# Adafruit_SharpMemoryDisplay.net
KiCad netlist of a schematic drawn in EAGLE
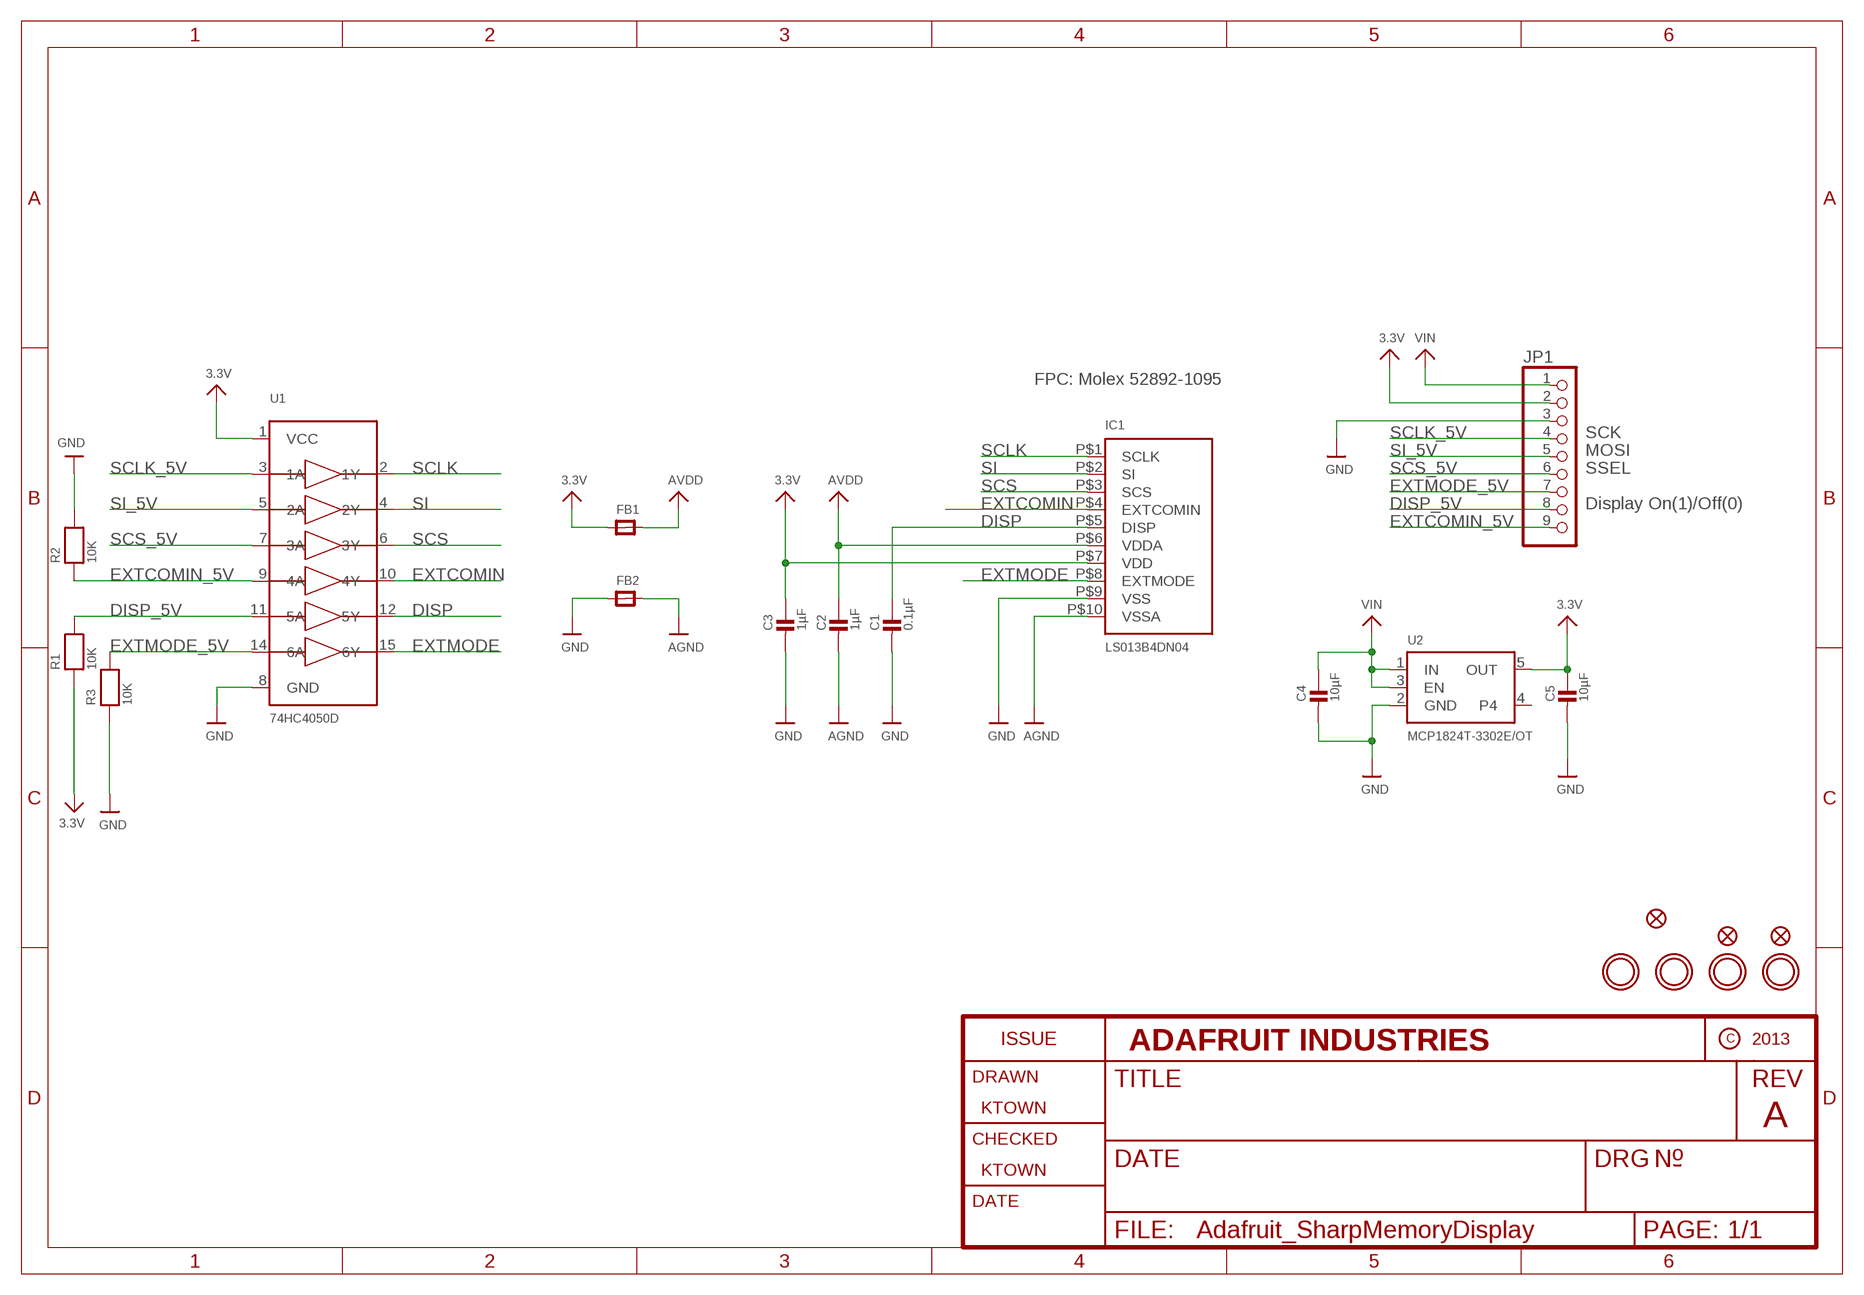
[diagram p0: schematic, sheet 1]

(export (version "E")
  (design (tool "Eeschema 10.0.6"))
  (components
    (comp (ref "C1")
      (value "0.1µF")
      (footprint "eagle-import:_0805")
      (libsource (lib "eagle-import") (part "CAP_CERAMIC_0805"))
    )
    (comp (ref "C2")
      (value "1µF")
      (footprint "eagle-import:_0805")
      (libsource (lib "eagle-import") (part "CAP_CERAMIC_0805"))
    )
    (comp (ref "C3")
      (value "1µF")
      (footprint "eagle-import:_0805")
      (libsource (lib "eagle-import") (part "CAP_CERAMIC_0805"))
    )
    (comp (ref "C4")
      (value "10µF")
      (footprint "eagle-import:_0805")
      (libsource (lib "eagle-import") (part "CAP_CERAMIC_0805"))
    )
    (comp (ref "C5")
      (value "10µF")
      (footprint "eagle-import:_0805")
      (libsource (lib "eagle-import") (part "CAP_CERAMIC_0805"))
    )
    (comp (ref "FB1")
      (value "FERRITE_0805")
      (footprint "eagle-import:_0805")
      (libsource (lib "eagle-import") (part "FERRITE_0805"))
    )
    (comp (ref "FB2")
      (value "FERRITE_0805")
      (footprint "eagle-import:_0805")
      (libsource (lib "eagle-import") (part "FERRITE_0805"))
    )
    (comp (ref "FID1")
      (value "FIDUCIAL\"\"")
      (footprint "eagle-import:FIDUCIAL_1MM")
      (libsource (lib "eagle-import") (part "FIDUCIAL{dblquote}{dblquote}"))
    )
    (comp (ref "FID2")
      (value "FIDUCIAL\"\"")
      (footprint "eagle-import:FIDUCIAL_1MM")
      (libsource (lib "eagle-import") (part "FIDUCIAL{dblquote}{dblquote}"))
    )
    (comp (ref "FID3")
      (value "FIDUCIAL\"\"")
      (footprint "eagle-import:FIDUCIAL_1MM")
      (libsource (lib "eagle-import") (part "FIDUCIAL{dblquote}{dblquote}"))
    )
    (comp (ref "IC1")
      (value "LS013B4DN04")
      (footprint "eagle-import:FPC_10PIN_52892-1095")
      (libsource (lib "eagle-import") (part "SHARP_MEMORYLCD_10PIN"))
    )
    (comp (ref "JP1")
      (value "HEADER-1X970MIL")
      (footprint "eagle-import:1X09_ROUND_70")
      (libsource (lib "eagle-import") (part "HEADER-1X970MIL"))
    )
    (comp (ref "R1")
      (value "10K")
      (footprint "eagle-import:_0805")
      (libsource (lib "eagle-import") (part "RESISTOR_0805"))
    )
    (comp (ref "R2")
      (value "10K")
      (footprint "eagle-import:_0805")
      (libsource (lib "eagle-import") (part "RESISTOR_0805"))
    )
    (comp (ref "R3")
      (value "10K")
      (footprint "eagle-import:_0805")
      (libsource (lib "eagle-import") (part "RESISTOR_0805"))
    )
    (comp (ref "U$21")
      (value "MOUNTINGHOLE3.0THIN")
      (footprint "eagle-import:MOUNTINGHOLE_3.0_PLATEDTHIN")
      (libsource (lib "eagle-import") (part "MOUNTINGHOLE3.0THIN"))
    )
    (comp (ref "U$22")
      (value "MOUNTINGHOLE3.0THIN")
      (footprint "eagle-import:MOUNTINGHOLE_3.0_PLATEDTHIN")
      (libsource (lib "eagle-import") (part "MOUNTINGHOLE3.0THIN"))
    )
    (comp (ref "U$27")
      (value "MOUNTINGHOLE3.0THIN")
      (footprint "eagle-import:MOUNTINGHOLE_3.0_PLATEDTHIN")
      (libsource (lib "eagle-import") (part "MOUNTINGHOLE3.0THIN"))
    )
    (comp (ref "U$28")
      (value "MOUNTINGHOLE3.0THIN")
      (footprint "eagle-import:MOUNTINGHOLE_3.0_PLATEDTHIN")
      (libsource (lib "eagle-import") (part "MOUNTINGHOLE3.0THIN"))
    )
    (comp (ref "U1")
      (value "74HC4050D")
      (footprint "eagle-import:SOIC16")
      (libsource (lib "eagle-import") (part "74HC4050D"))
    )
    (comp (ref "U2")
      (value "MCP1824T-3302E/OT")
      (footprint "eagle-import:SOT23-5")
      (libsource (lib "eagle-import") (part "VREG_SOT23-5"))
    )
  )
  (nets
    (net (code "1") (name "/DISP") (class "Default")
      (node (ref "C1") (pin "1") (pinfunction "P$1_1") (pintype "passive"))
      (node (ref "IC1") (pin "P$5") (pinfunction "DISP_P$5") (pintype "input"))
      (node (ref "U1") (pin "12") (pinfunction "5Y_12") (pintype "bidirectional"))
    )
    (net (code "2") (name "/DISP_5V") (class "Default")
      (node (ref "JP1") (pin "8") (pinfunction "8_8") (pintype "passive"))
      (node (ref "R1") (pin "2") (pinfunction "2_2") (pintype "passive"))
      (node (ref "U1") (pin "11") (pinfunction "5A_11") (pintype "bidirectional"))
    )
    (net (code "3") (name "/EXTCOMIN") (class "Default")
      (node (ref "IC1") (pin "P$4") (pinfunction "EXTCOMIN_P$4") (pintype "input"))
      (node (ref "U1") (pin "10") (pinfunction "4Y_10") (pintype "bidirectional"))
    )
    (net (code "4") (name "/EXTCOMIN_5V") (class "Default")
      (node (ref "JP1") (pin "9") (pinfunction "9_9") (pintype "passive"))
      (node (ref "R2") (pin "1") (pinfunction "1_1") (pintype "passive"))
      (node (ref "U1") (pin "9") (pinfunction "4A_9") (pintype "bidirectional"))
    )
    (net (code "5") (name "/EXTMODE") (class "Default")
      (node (ref "IC1") (pin "P$8") (pinfunction "EXTMODE_P$8") (pintype "input"))
      (node (ref "U1") (pin "15") (pinfunction "6Y_15") (pintype "bidirectional"))
    )
    (net (code "6") (name "/EXTMODE_5V") (class "Default")
      (node (ref "JP1") (pin "7") (pinfunction "7_7") (pintype "passive"))
      (node (ref "R3") (pin "2") (pinfunction "2_2") (pintype "passive"))
      (node (ref "U1") (pin "14") (pinfunction "6A_14") (pintype "bidirectional"))
    )
    (net (code "7") (name "/SCLK") (class "Default")
      (node (ref "IC1") (pin "P$1") (pinfunction "SCLK_P$1") (pintype "input"))
      (node (ref "U1") (pin "2") (pinfunction "1Y_2") (pintype "bidirectional"))
    )
    (net (code "8") (name "/SCLK_5V") (class "Default")
      (node (ref "JP1") (pin "4") (pinfunction "4_4") (pintype "passive"))
      (node (ref "U1") (pin "3") (pinfunction "1A_3") (pintype "bidirectional"))
    )
    (net (code "9") (name "/SCS") (class "Default")
      (node (ref "IC1") (pin "P$3") (pinfunction "SCS_P$3") (pintype "input"))
      (node (ref "U1") (pin "6") (pinfunction "3Y_6") (pintype "bidirectional"))
    )
    (net (code "10") (name "/SCS_5V") (class "Default")
      (node (ref "JP1") (pin "6") (pinfunction "6_6") (pintype "passive"))
      (node (ref "U1") (pin "7") (pinfunction "3A_7") (pintype "bidirectional"))
    )
    (net (code "11") (name "/SI") (class "Default")
      (node (ref "IC1") (pin "P$2") (pinfunction "SI_P$2") (pintype "input"))
      (node (ref "U1") (pin "4") (pinfunction "2Y_4") (pintype "bidirectional"))
    )
    (net (code "12") (name "/SI_5V") (class "Default")
      (node (ref "JP1") (pin "5") (pinfunction "5_5") (pintype "passive"))
      (node (ref "U1") (pin "5") (pinfunction "2A_5") (pintype "bidirectional"))
    )
    (net (code "13") (name "3.3V") (class "Default")
      (node (ref "C3") (pin "1") (pinfunction "P$1_1") (pintype "passive"))
      (node (ref "C5") (pin "1") (pinfunction "P$1_1") (pintype "passive"))
      (node (ref "FB1") (pin "1") (pinfunction "P$1_1") (pintype "passive"))
      (node (ref "IC1") (pin "P$7") (pinfunction "VDD_P$7") (pintype "power_in"))
      (node (ref "JP1") (pin "2") (pinfunction "2_2") (pintype "passive"))
      (node (ref "R1") (pin "1") (pinfunction "1_1") (pintype "passive"))
      (node (ref "U1") (pin "1") (pinfunction "VCC_1") (pintype "bidirectional"))
      (node (ref "U2") (pin "5") (pinfunction "OUT_5") (pintype "power_in"))
    )
    (net (code "14") (name "AGND") (class "Default")
      (node (ref "C2") (pin "2") (pinfunction "P$2_2") (pintype "passive"))
      (node (ref "FB2") (pin "2") (pinfunction "P$2_2") (pintype "passive"))
      (node (ref "IC1") (pin "P$10") (pinfunction "VSSA_P$10") (pintype "power_in"))
    )
    (net (code "15") (name "AVDD") (class "Default")
      (node (ref "C2") (pin "1") (pinfunction "P$1_1") (pintype "passive"))
      (node (ref "FB1") (pin "2") (pinfunction "P$2_2") (pintype "passive"))
      (node (ref "IC1") (pin "P$6") (pinfunction "VDDA_P$6") (pintype "power_in"))
    )
    (net (code "16") (name "GND") (class "Default")
      (node (ref "C1") (pin "2") (pinfunction "P$2_2") (pintype "passive"))
      (node (ref "C3") (pin "2") (pinfunction "P$2_2") (pintype "passive"))
      (node (ref "C4") (pin "2") (pinfunction "P$2_2") (pintype "passive"))
      (node (ref "C5") (pin "2") (pinfunction "P$2_2") (pintype "passive"))
      (node (ref "FB2") (pin "1") (pinfunction "P$1_1") (pintype "passive"))
      (node (ref "IC1") (pin "P$9") (pinfunction "VSS_P$9") (pintype "power_in"))
      (node (ref "JP1") (pin "3") (pinfunction "3_3") (pintype "passive"))
      (node (ref "R2") (pin "2") (pinfunction "2_2") (pintype "passive"))
      (node (ref "R3") (pin "1") (pinfunction "1_1") (pintype "passive"))
      (node (ref "U1") (pin "8") (pinfunction "GND_8") (pintype "bidirectional"))
      (node (ref "U2") (pin "2") (pinfunction "GND_2") (pintype "power_in"))
    )
    (net (code "17") (name "VIN") (class "Default")
      (node (ref "C4") (pin "1") (pinfunction "P$1_1") (pintype "passive"))
      (node (ref "JP1") (pin "1") (pinfunction "1_1") (pintype "passive"))
      (node (ref "U2") (pin "1") (pinfunction "IN_1") (pintype "power_in"))
      (node (ref "U2") (pin "3") (pinfunction "EN_3") (pintype "input"))
    )
    (net (code "18") (name "unconnected-(U2-P4-Pad4)") (class "Default")
      (node (ref "U2") (pin "4") (pinfunction "P4_4") (pintype "bidirectional"))
    )
  )
)
